# MP8756GD_3.net
KiCad netlist of a schematic drawn in Altium Designer
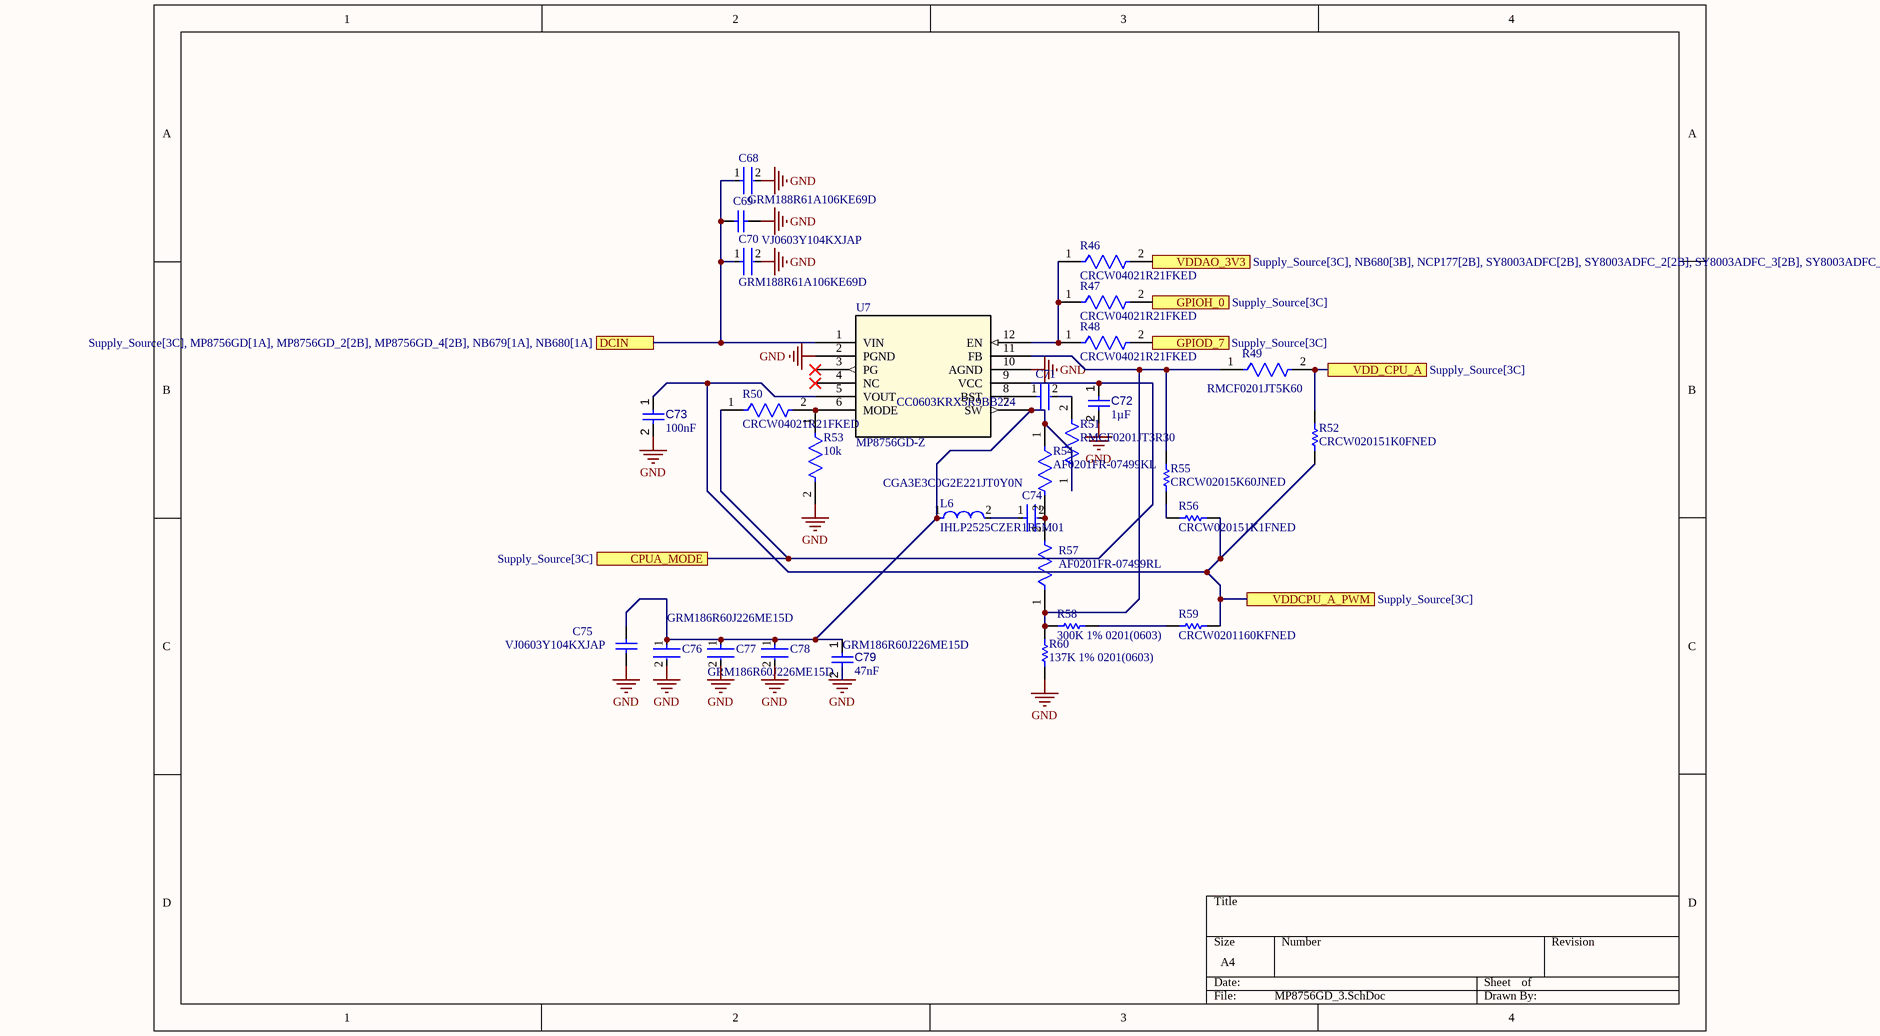
[diagram p0: MP8756GD_3.SchDoc]

(export (version "E")
  (design (tool "Eeschema 10.0.6"))
  (components
    (comp (ref "C68")
      (value "GRM188R61A106KE69D")
      (footprint "FP-GRM18-0_15-MFG")
      (description "CAP CER 10UF 10V X5R 0603")
      (fields
        (field (name "OCTOPART") "https://octopart.com/grm188r61a106ke69d-murata-22851381")
        (field (name "MANUFACTURER") "Murata")
      )
      (libsource (lib "Altium Content Vault") (part "11868f565c42a9108669ba33697ecf6"))
    )
    (comp (ref "C69")
      (value "VJ0603Y104KXJAP")
      (footprint "CAPC1608X92X38NL15T08")
      (fields (field (name "MANUFACTURER") "Vitramon"))
      (libsource (lib "Altium Content Vault") (part "CAP"))
    )
    (comp (ref "C70")
      (value "GRM188R61A106KE69D")
      (footprint "FP-GRM18-0_15-MFG")
      (description "CAP CER 10UF 10V X5R 0603")
      (fields
        (field (name "OCTOPART") "https://octopart.com/grm188r61a106ke69d-murata-22851381")
        (field (name "MANUFACTURER") "Murata")
      )
      (libsource (lib "Altium Content Vault") (part "11868f565c42a9108669ba33697ecf6"))
    )
    (comp (ref "C71")
      (value "CC0603KRX5R9BB224")
      (footprint "FP-CC0603-DA-MFG")
      (description "CC0603 220 nF X5R 10.00% 50 V")
      (fields
        (field (name "TOLERANCE") "0.1")
        (field (name "OCTOPART") "https://octopart.com/cc0603krx5r9bb224-yageo-90326743")
      )
      (libsource (lib "Altium Content Vault") (part "11868f565c42a9108669ba33697ecf6"))
    )
    (comp (ref "C72")
      (value "1µF")
      (footprint "CAPC1005X55X25LL05T10")
      (description "Chip Capacitor, 1 uF, +/- 10%, 6.3 V, 0402 (1005 Metric)")
      (fields (field (name "TOLERANCE") "10%") (field (name "Comment") "Capacitor 1 uF +/- 10% 6.3 V 0402"))
      (libsource (lib "MIGUEL ANGEL ALVAREZ GUZMAN") (part "CAP-NP-2"))
    )
    (comp (ref "C73")
      (value "100nF")
      (footprint "CAPC1005X56X25LL10T15")
      (description "Chip Capacitor, 0.1 uF, +/- 5%, 16 V, 0402 (1005 Metric)")
      (fields (field (name "TOLERANCE") "5%") (field (name "Comment") "Capacitor 0.1 uF +/- 5% 16 V 0402"))
      (libsource (lib "MIGUEL ANGEL ALVAREZ GUZMAN") (part "CAP-NP-2"))
    )
    (comp (ref "C74")
      (value "CGA3E3C0G2E221JT0Y0N")
      (footprint "FP-CGA3E-0_3-0_1-IPC_B")
      (description "Cap Ceramic 220pF 250V C0G 5% Pad SMD 0603 +125°C Automotive T/R")
      (libsource (lib "Altium Content Vault") (part "b4654b650e69147ec39a6b967a45e02"))
    )
    (comp (ref "C75")
      (value "VJ0603Y104KXJAP")
      (footprint "CAPC1608X92X38NL15T08")
      (fields (field (name "MANUFACTURER") "Vitramon"))
      (libsource (lib "Altium Content Vault") (part "CAP"))
    )
    (comp (ref "C76")
      (value "GRM186R60J226ME15D")
      (footprint "FP-GRM186-0_2-IPC_B")
      (description "Chip Multilayer Ceramic Capacitors for General Purpose, 0603, 22uF, X5R, 15%, 20%, 6.3V")
      (fields (field (name "TOLERANCE") "20%"))
      (libsource (lib "Altium Content Vault") (part "02cd4be3c70576c341d710602a673aa"))
    )
    (comp (ref "C77")
      (value "GRM186R60J226ME15D")
      (footprint "FP-GRM186-0_2-IPC_B")
      (description "Chip Multilayer Ceramic Capacitors for General Purpose, 0603, 22uF, X5R, 15%, 20%, 6.3V")
      (fields (field (name "TOLERANCE") "20%"))
      (libsource (lib "Altium Content Vault") (part "02cd4be3c70576c341d710602a673aa"))
    )
    (comp (ref "C78")
      (value "GRM186R60J226ME15D")
      (footprint "FP-GRM186-0_2-IPC_B")
      (description "Chip Multilayer Ceramic Capacitors for General Purpose, 0603, 22uF, X5R, 15%, 20%, 6.3V")
      (fields (field (name "TOLERANCE") "20%"))
      (libsource (lib "Altium Content Vault") (part "02cd4be3c70576c341d710602a673aa"))
    )
    (comp (ref "C79")
      (value "47nF")
      (footprint "CAPC0402(1005)60_L")
      (description "Chip Capacitor, 47nF +/-20%, 50V, 0402, Thickness 0.6 mm")
      (fields (field (name "TOLERANCE") "20%") (field (name "Comment") "Capacitor 47nF +/-20% 50V 0402"))
      (libsource (lib "MIGUEL ANGEL ALVAREZ GUZMAN") (part "CAP-NP-2"))
    )
    (comp (ref "L6")
      (value "IHLP2525CZER1R5M01")
      (footprint "FP-IHLP-2525CZ-FP_2_413x3-MFG")
      (description "Commercial Inductors, High Saturation Series 1.5uH 9A 15mΩ 20%")
      (fields (field (name "TOLERANCE") "20%"))
      (libsource (lib "Altium Content Vault") (part "725321dda6339637d4d059423bc1c3c"))
    )
    (comp (ref "R46")
      (value "CRCW04021R21FKED")
      (footprint "FP-CRCW0402-e3-MFG")
      (description "RES Thick Film, 1.21Ω, 1%, 0.063W, 100ppm/°C, 0402")
      (fields (field (name "TOLERANCE") "1%"))
      (libsource (lib "Altium Content Vault") (part "1029c3af85768c4190bb7ad29bc67b5"))
    )
    (comp (ref "R47")
      (value "CRCW04021R21FKED")
      (footprint "FP-CRCW0402-e3-MFG")
      (description "RES Thick Film, 1.21Ω, 1%, 0.063W, 100ppm/°C, 0402")
      (fields (field (name "TOLERANCE") "1%"))
      (libsource (lib "Altium Content Vault") (part "1029c3af85768c4190bb7ad29bc67b5"))
    )
    (comp (ref "R48")
      (value "CRCW04021R21FKED")
      (footprint "FP-CRCW0402-e3-MFG")
      (description "RES Thick Film, 1.21Ω, 1%, 0.063W, 100ppm/°C, 0402")
      (fields (field (name "TOLERANCE") "1%"))
      (libsource (lib "Altium Content Vault") (part "1029c3af85768c4190bb7ad29bc67b5"))
    )
    (comp (ref "R49")
      (value "RMCF0201JT5K60")
      (footprint "FP-RMCF0201-MFG")
      (description "5.6kΩ ±5% 0.05W 0201 Thick Film Chip Resistor AEC-Q200 compliant")
      (fields (field (name "TOLERANCE") "5%"))
      (libsource (lib "Altium Content Vault") (part "1029c3af85768c4190bb7ad29bc67b5"))
    )
    (comp (ref "R50")
      (value "CRCW04021R21FKED")
      (footprint "FP-CRCW0402-e3-MFG")
      (description "RES Thick Film, 1.21Ω, 1%, 0.063W, 100ppm/°C, 0402")
      (fields (field (name "TOLERANCE") "1%"))
      (libsource (lib "Altium Content Vault") (part "1029c3af85768c4190bb7ad29bc67b5"))
    )
    (comp (ref "R51")
      (value "RMCF0201JT3R30")
      (footprint "FP-RMCF0201-IPC_A")
      (description "3.3Ω ±5% 0.05W 0201 Thick Film Chip Resistor AEC-Q200 compliant")
      (fields (field (name "TOLERANCE") "5%"))
      (libsource (lib "Altium Content Vault") (part "1029c3af85768c4190bb7ad29bc67b5"))
    )
    (comp (ref "R52")
      (value "CRCW020151K0FNED")
      (footprint "RESC0603X28X15LL05T05")
      (fields (field (name "MANUFACTURER") "Vishay Dale"))
      (libsource (lib "Altium Content Vault") (part "RES"))
    )
    (comp (ref "R53")
      (value "10k")
      (footprint "FP-RT0201-IPC_C")
      (description "Fixed Resistor, Thin Film, 0.05W, 10000ohm, 25V, 0.1% +/-Tol, 50ppm/Cel, Surface Mount, 0201")
      (fields (field (name "TOLERANCE") "0.1%") (field (name "Comment") "RT0201BRE0710KL"))
      (libsource (lib "MIGUEL ANGEL ALVAREZ GUZMAN") (part "1029c3af85768c4190bb7ad29bc67b5"))
    )
    (comp (ref "R54")
      (value "AF0201FR-07499KL")
      (footprint "FP-AF0201-MFG")
      (description "Anti-Sulfurated Chip Resistors Automotive Grade 499kΩ 1% 200ppm/°C 0201")
      (fields (field (name "TOLERANCE") "1%"))
      (libsource (lib "Altium Content Vault") (part "1029c3af85768c4190bb7ad29bc67b5"))
    )
    (comp (ref "R55")
      (value "CRCW02015K60JNED")
      (footprint "RESC0603X28X15NL05T05")
      (fields (field (name "MANUFACTURER") "Vishay Dale"))
      (libsource (lib "Altium Content Vault") (part "RES"))
    )
    (comp (ref "R56")
      (value "CRCW020151K1FNED")
      (footprint "RESC0603X28X15ML05T05")
      (fields (field (name "MANUFACTURER") "Vishay Dale"))
      (libsource (lib "Altium Content Vault") (part "RES"))
    )
    (comp (ref "R57")
      (value "AF0201FR-07499RL")
      (footprint "FP-AF0201-IPC_A")
      (description "Anti-Sulfurated Chip Resistors Automotive Grade 499Ω 1% 200ppm/°C 0201")
      (fields (field (name "TOLERANCE") "1%"))
      (libsource (lib "Altium Content Vault") (part "1029c3af85768c4190bb7ad29bc67b5"))
    )
    (comp (ref "R58")
      (value "300K 1% 0201(0603)")
      (footprint "RESC0201(0603)_L")
      (description "300K 0.05W 1% 0201 (0603 Metric)  SMD")
      (fields (field (name "POWER") "0.05 W") (field (name "TOLERANCE") "1 %"))
      (libsource (lib "Altium Content Vault") (part "RES"))
    )
    (comp (ref "R59")
      (value "CRCW0201160KFNED")
      (footprint "RESC0603X28X15ML05T05")
      (fields (field (name "MANUFACTURER") "Vishay Dale"))
      (libsource (lib "Altium Content Vault") (part "RES"))
    )
    (comp (ref "R60")
      (value "137K 1% 0201(0603)")
      (footprint "RESC0201(0603)_M")
      (description "137K 0.05W 1% 0201 (0603 Metric)  SMD")
      (fields (field (name "POWER") "0.05 W") (field (name "TOLERANCE") "1 %"))
      (libsource (lib "Altium Content Vault") (part "RES"))
    )
    (comp (ref "U7")
      (value "MP8756GD-Z")
      (footprint "QFN-12_MP8756_MNP")
      (description "26V 6A Low IQ High-Current Synchronous Step-Down Converter")
      (fields (field (name "COPYRIGHT") "Copyright (C) 2025 Ultra Librarian. All rights reserved."))
      (libsource (lib "MIGUEL ANGEL ALVAREZ GUZMAN") (part "MP8756GD-Z"))
    )
  )
  (nets
    (net (code "1") (name "/CPUA_MODE") (class "Default")
      (node (ref "C72") (pin "1") (pinfunction "1_1") (pintype "passive"))
      (node (ref "R50") (pin "1") (pinfunction "1_1") (pintype "passive"))
      (node (ref "U7") (pin "9") (pinfunction "VCC_9") (pintype "power_in"))
    )
    (net (code "2") (name "/DCIN") (class "Default")
      (node (ref "C68") (pin "1") (pinfunction "1_1") (pintype "passive"))
      (node (ref "C69") (pin "2") (pinfunction "2_2") (pintype "passive"))
      (node (ref "C70") (pin "1") (pinfunction "1_1") (pintype "passive"))
      (node (ref "U7") (pin "1") (pinfunction "VIN_1") (pintype "power_in"))
    )
    (net (code "3") (name "/GPIOD_7") (class "Default")
      (node (ref "R48") (pin "2") (pinfunction "2_2") (pintype "passive"))
    )
    (net (code "4") (name "/GPIOH_0") (class "Default")
      (node (ref "R47") (pin "2") (pinfunction "2_2") (pintype "passive"))
    )
    (net (code "5") (name "/VDDAO_3V3") (class "Default")
      (node (ref "R46") (pin "2") (pinfunction "2_2") (pintype "passive"))
    )
    (net (code "6") (name "/VDDCPU_A_PWM") (class "Default")
      (node (ref "C73") (pin "1") (pinfunction "1_1") (pintype "passive"))
      (node (ref "R52") (pin "2") (pinfunction "2_2") (pintype "passive"))
      (node (ref "R56") (pin "2") (pinfunction "2_2") (pintype "passive"))
      (node (ref "R59") (pin "2") (pinfunction "2_2") (pintype "passive"))
      (node (ref "U7") (pin "5") (pinfunction "VOUT_5") (pintype "power_in"))
    )
    (net (code "7") (name "/VDD_CPU_A") (class "Default")
      (node (ref "R49") (pin "2") (pinfunction "2_2") (pintype "passive"))
      (node (ref "R52") (pin "1") (pinfunction "1_1") (pintype "passive"))
    )
    (net (code "8") (name "GND") (class "Default")
      (node (ref "C68") (pin "2") (pinfunction "2_2") (pintype "passive"))
      (node (ref "C69") (pin "1") (pinfunction "1_1") (pintype "passive"))
      (node (ref "C70") (pin "2") (pinfunction "2_2") (pintype "passive"))
      (node (ref "C72") (pin "2") (pinfunction "2_2") (pintype "passive"))
      (node (ref "C73") (pin "2") (pinfunction "2_2") (pintype "passive"))
      (node (ref "C75") (pin "1") (pinfunction "1_1") (pintype "passive"))
      (node (ref "C76") (pin "2") (pinfunction "2_2") (pintype "passive"))
      (node (ref "C77") (pin "2") (pinfunction "2_2") (pintype "passive"))
      (node (ref "C78") (pin "2") (pinfunction "2_2") (pintype "passive"))
      (node (ref "C79") (pin "2") (pinfunction "2_2") (pintype "passive"))
      (node (ref "R53") (pin "2") (pinfunction "2_2") (pintype "passive"))
      (node (ref "R60") (pin "1") (pinfunction "1_1") (pintype "passive"))
      (node (ref "U7") (pin "10") (pinfunction "AGND_10") (pintype "power_in"))
      (node (ref "U7") (pin "2") (pinfunction "PGND_2") (pintype "power_in"))
    )
    (net (code "9") (name "Net-(C71-Pad2)") (class "Default")
      (node (ref "C71") (pin "2") (pinfunction "2_2") (pintype "passive"))
      (node (ref "R51") (pin "2") (pinfunction "2_2") (pintype "passive"))
    )
    (net (code "10") (name "Net-(C74-Pad1)") (class "Default")
      (node (ref "C74") (pin "1") (pinfunction "1_1") (pintype "passive"))
      (node (ref "L6") (pin "2") (pinfunction "2_2") (pintype "passive"))
    )
    (net (code "11") (name "Net-(C74-Pad2)") (class "Default")
      (node (ref "C74") (pin "2") (pinfunction "2_2") (pintype "passive"))
      (node (ref "R54") (pin "2") (pinfunction "2_2") (pintype "passive"))
      (node (ref "R57") (pin "2") (pinfunction "2_2") (pintype "passive"))
    )
    (net (code "12") (name "Net-(R55-Pad2)") (class "Default")
      (node (ref "R55") (pin "2") (pinfunction "2_2") (pintype "passive"))
      (node (ref "R56") (pin "1") (pinfunction "1_1") (pintype "passive"))
    )
    (net (code "13") (name "Net-(R58-Pad2)") (class "Default")
      (node (ref "R58") (pin "2") (pinfunction "2_2") (pintype "passive"))
      (node (ref "R59") (pin "1") (pinfunction "1_1") (pintype "passive"))
    )
    (net (code "14") (name "Net-(U7-BST)") (class "Default")
      (node (ref "C71") (pin "1") (pinfunction "1_1") (pintype "passive"))
      (node (ref "U7") (pin "8") (pinfunction "BST_8") (pintype "power_in"))
    )
    (net (code "15") (name "Net-(U7-EN)") (class "Default")
      (node (ref "R46") (pin "1") (pinfunction "1_1") (pintype "passive"))
      (node (ref "R47") (pin "1") (pinfunction "1_1") (pintype "passive"))
      (node (ref "R48") (pin "1") (pinfunction "1_1") (pintype "passive"))
      (node (ref "U7") (pin "12") (pinfunction "EN_12") (pintype "input"))
    )
    (net (code "16") (name "Net-(U7-FB)") (class "Default")
      (node (ref "R49") (pin "1") (pinfunction "1_1") (pintype "passive"))
      (node (ref "R55") (pin "1") (pinfunction "1_1") (pintype "passive"))
      (node (ref "R57") (pin "1") (pinfunction "1_1") (pintype "passive"))
      (node (ref "R58") (pin "1") (pinfunction "1_1") (pintype "passive"))
      (node (ref "R60") (pin "2") (pinfunction "2_2") (pintype "passive"))
      (node (ref "U7") (pin "11") (pinfunction "FB_11") (pintype "passive"))
    )
    (net (code "17") (name "Net-(U7-MODE)") (class "Default")
      (node (ref "R50") (pin "2") (pinfunction "2_2") (pintype "passive"))
      (node (ref "R53") (pin "1") (pinfunction "1_1") (pintype "passive"))
      (node (ref "U7") (pin "6") (pinfunction "MODE_6") (pintype "passive"))
    )
    (net (code "18") (name "Net-(U7-SW)") (class "Default")
      (node (ref "C75") (pin "2") (pinfunction "2_2") (pintype "passive"))
      (node (ref "C76") (pin "1") (pinfunction "1_1") (pintype "passive"))
      (node (ref "C77") (pin "1") (pinfunction "1_1") (pintype "passive"))
      (node (ref "C78") (pin "1") (pinfunction "1_1") (pintype "passive"))
      (node (ref "C79") (pin "1") (pinfunction "1_1") (pintype "passive"))
      (node (ref "L6") (pin "1") (pinfunction "1_1") (pintype "passive"))
      (node (ref "R51") (pin "1") (pinfunction "1_1") (pintype "passive"))
      (node (ref "R54") (pin "1") (pinfunction "1_1") (pintype "passive"))
      (node (ref "U7") (pin "7") (pinfunction "SW_7") (pintype "output"))
    )
    (net (code "19") (name "unconnected-(U7-NC-Pad4)") (class "Default")
      (node (ref "U7") (pin "4") (pinfunction "NC_4") (pintype "passive+no_connect"))
    )
    (net (code "20") (name "unconnected-(U7-PG-Pad3)") (class "Default")
      (node (ref "U7") (pin "3") (pinfunction "PG_3") (pintype "output+no_connect"))
    )
  )
)
